# BalancingRobotFullSizePCB.net
KiCad netlist of a schematic drawn in EAGLE
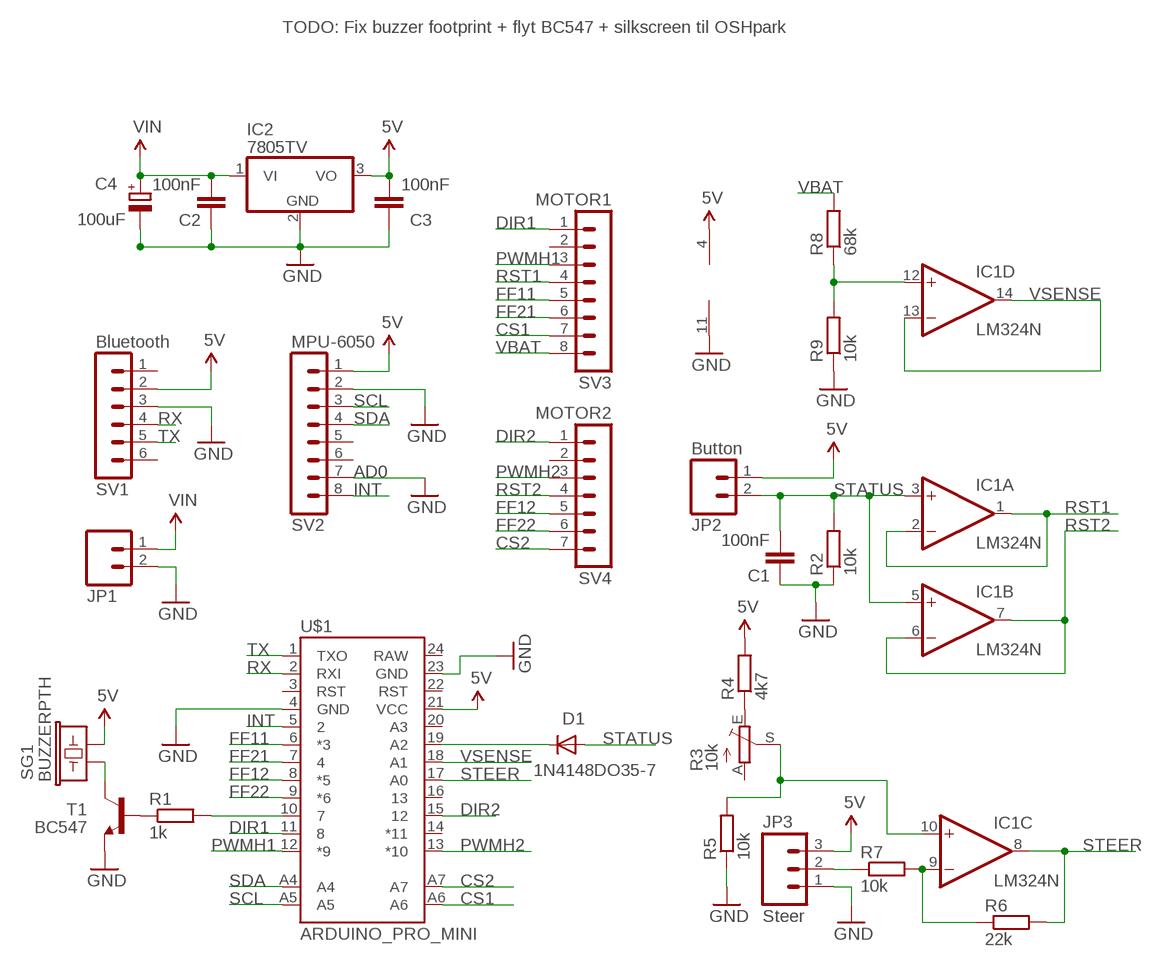
[diagram p0: schematic, sheet 1]

(export (version "E")
  (design (tool "Eeschema 10.0.6"))
  (components
    (comp (ref "C1")
      (value "100nF")
      (footprint "eagle-import:C025-025X050")
      (libsource (lib "eagle-import") (part "C-EU025-025X050"))
    )
    (comp (ref "C2")
      (value "100nF")
      (footprint "eagle-import:C025-025X050")
      (libsource (lib "eagle-import") (part "C-EU025-025X050"))
    )
    (comp (ref "C3")
      (value "100nF")
      (footprint "eagle-import:C025-025X050")
      (libsource (lib "eagle-import") (part "C-EU025-025X050"))
    )
    (comp (ref "C4")
      (value "100uF")
      (footprint "eagle-import:E2,5-5")
      (libsource (lib "eagle-import") (part "CPOL-EUE2.5-5"))
    )
    (comp (ref "D1")
      (value "1N4148DO35-7")
      (footprint "eagle-import:DO35-7")
      (libsource (lib "eagle-import") (part "1N4148DO35-7"))
    )
    (comp (ref "IC1")
      (value "LM324N")
      (footprint "eagle-import:DIL14")
      (libsource (lib "eagle-import") (part "LM324N"))
    )
    (comp (ref "IC2")
      (value "7805TV")
      (footprint "eagle-import:TO220V")
      (libsource (lib "eagle-import") (part "78TV05"))
    )
    (comp (ref "JP1")
      (value "M02PTH")
      (footprint "eagle-import:1X02")
      (libsource (lib "eagle-import") (part "M02PTH"))
    )
    (comp (ref "JP2")
      (value "Button")
      (footprint "eagle-import:1X02")
      (libsource (lib "eagle-import") (part "M02PTH"))
    )
    (comp (ref "JP3")
      (value "Steer")
      (footprint "eagle-import:1X03")
      (libsource (lib "eagle-import") (part "M03PTH"))
    )
    (comp (ref "R1")
      (value "1k")
      (footprint "eagle-import:0207_10")
      (libsource (lib "eagle-import") (part "R-EU_0207/10"))
    )
    (comp (ref "R2")
      (value "10k")
      (footprint "eagle-import:0207_10")
      (libsource (lib "eagle-import") (part "R-EU_0207/10"))
    )
    (comp (ref "R3")
      (value "10k")
      (footprint "eagle-import:B25P")
      (libsource (lib "eagle-import") (part "TRIM_EU-B25P"))
    )
    (comp (ref "R4")
      (value "4k7")
      (footprint "eagle-import:0207_10")
      (libsource (lib "eagle-import") (part "R-EU_0207/10"))
    )
    (comp (ref "R5")
      (value "10k")
      (footprint "eagle-import:0207_10")
      (libsource (lib "eagle-import") (part "R-EU_0207/10"))
    )
    (comp (ref "R6")
      (value "22k")
      (footprint "eagle-import:0207_10")
      (libsource (lib "eagle-import") (part "R-EU_0207/10"))
    )
    (comp (ref "R7")
      (value "10k")
      (footprint "eagle-import:0207_10")
      (libsource (lib "eagle-import") (part "R-EU_0207/10"))
    )
    (comp (ref "R8")
      (value "68k")
      (footprint "eagle-import:0207_10")
      (libsource (lib "eagle-import") (part "R-EU_0207/10"))
    )
    (comp (ref "R9")
      (value "10k")
      (footprint "eagle-import:0207_10")
      (libsource (lib "eagle-import") (part "R-EU_0207/10"))
    )
    (comp (ref "SG1")
      (value "BUZZERPTH")
      (footprint "eagle-import:BUZZER-12MM")
      (libsource (lib "eagle-import") (part "BUZZERPTH"))
    )
    (comp (ref "SV1")
      (value "Bluetooth")
      (footprint "eagle-import:MA06-1")
      (libsource (lib "eagle-import") (part "MA06-1"))
    )
    (comp (ref "SV2")
      (value "MPU-6050")
      (footprint "eagle-import:MA08-1")
      (libsource (lib "eagle-import") (part "MA08-1"))
    )
    (comp (ref "SV3")
      (value "MOTOR1")
      (footprint "eagle-import:MA08-1")
      (libsource (lib "eagle-import") (part "MA08-1"))
    )
    (comp (ref "SV4")
      (value "MOTOR2")
      (footprint "eagle-import:MA07-1")
      (libsource (lib "eagle-import") (part "MA07-1"))
    )
    (comp (ref "T1")
      (value "BC547")
      (footprint "eagle-import:TO92")
      (libsource (lib "eagle-import") (part "BC547"))
    )
    (comp (ref "U$1")
      (value "ARDUINO_PRO_MINI")
      (footprint "eagle-import:ARDUINO_PRO_MINI")
      (libsource (lib "eagle-import") (part "ARDUINO_PRO_MINI"))
    )
  )
  (nets
    (net (code "1") (name "/CS1") (class "Default")
      (node (ref "SV3") (pin "7") (pinfunction "7_7") (pintype "passive"))
      (node (ref "U$1") (pin "A6") (pinfunction "A6_A6") (pintype "bidirectional"))
    )
    (net (code "2") (name "/CS2") (class "Default")
      (node (ref "SV4") (pin "7") (pinfunction "7_7") (pintype "passive"))
      (node (ref "U$1") (pin "A7") (pinfunction "A7_A7") (pintype "bidirectional"))
    )
    (net (code "3") (name "/DIR1") (class "Default")
      (node (ref "SV3") (pin "1") (pinfunction "1_1") (pintype "passive"))
      (node (ref "U$1") (pin "11") (pinfunction "8_11") (pintype "bidirectional"))
    )
    (net (code "4") (name "/DIR2") (class "Default")
      (node (ref "SV4") (pin "1") (pinfunction "1_1") (pintype "passive"))
      (node (ref "U$1") (pin "15") (pinfunction "12_15") (pintype "bidirectional"))
    )
    (net (code "5") (name "/FF11") (class "Default")
      (node (ref "SV3") (pin "5") (pinfunction "5_5") (pintype "passive"))
      (node (ref "U$1") (pin "6") (pinfunction "*3_6") (pintype "bidirectional"))
    )
    (net (code "6") (name "/FF12") (class "Default")
      (node (ref "SV4") (pin "5") (pinfunction "5_5") (pintype "passive"))
      (node (ref "U$1") (pin "8") (pinfunction "*5_8") (pintype "bidirectional"))
    )
    (net (code "7") (name "/FF21") (class "Default")
      (node (ref "SV3") (pin "6") (pinfunction "6_6") (pintype "passive"))
      (node (ref "U$1") (pin "7") (pinfunction "4_7") (pintype "bidirectional"))
    )
    (net (code "8") (name "/FF22") (class "Default")
      (node (ref "SV4") (pin "6") (pinfunction "6_6") (pintype "passive"))
      (node (ref "U$1") (pin "9") (pinfunction "*6_9") (pintype "bidirectional"))
    )
    (net (code "9") (name "/INT") (class "Default")
      (node (ref "SV2") (pin "8") (pinfunction "8_8") (pintype "passive"))
      (node (ref "U$1") (pin "5") (pinfunction "2_5") (pintype "bidirectional"))
    )
    (net (code "10") (name "/PWMH1") (class "Default")
      (node (ref "SV3") (pin "3") (pinfunction "3_3") (pintype "passive"))
      (node (ref "U$1") (pin "12") (pinfunction "*9_12") (pintype "bidirectional"))
    )
    (net (code "11") (name "/PWMH2") (class "Default")
      (node (ref "SV4") (pin "3") (pinfunction "3_3") (pintype "passive"))
      (node (ref "U$1") (pin "13") (pinfunction "*10_13") (pintype "bidirectional"))
    )
    (net (code "12") (name "/RST1") (class "Default")
      (node (ref "IC1") (pin "1") (pinfunction "OUT_1") (pintype "output"))
      (node (ref "IC1") (pin "2") (pinfunction "-IN_2") (pintype "input"))
      (node (ref "SV3") (pin "4") (pinfunction "4_4") (pintype "passive"))
    )
    (net (code "13") (name "/RST2") (class "Default")
      (node (ref "IC1") (pin "6") (pinfunction "-IN_6") (pintype "input"))
      (node (ref "IC1") (pin "7") (pinfunction "OUT_7") (pintype "output"))
      (node (ref "SV4") (pin "4") (pinfunction "4_4") (pintype "passive"))
    )
    (net (code "14") (name "/RX") (class "Default")
      (node (ref "SV1") (pin "4") (pinfunction "4_4") (pintype "passive"))
      (node (ref "U$1") (pin "2") (pinfunction "RXI_2") (pintype "bidirectional"))
    )
    (net (code "15") (name "/SCL") (class "Default")
      (node (ref "SV2") (pin "3") (pinfunction "3_3") (pintype "passive"))
      (node (ref "U$1") (pin "A5") (pinfunction "A5_A5") (pintype "bidirectional"))
    )
    (net (code "16") (name "/SDA") (class "Default")
      (node (ref "SV2") (pin "4") (pinfunction "4_4") (pintype "passive"))
      (node (ref "U$1") (pin "A4") (pinfunction "A4_A4") (pintype "bidirectional"))
    )
    (net (code "17") (name "/STATUS") (class "Default")
      (node (ref "C1") (pin "2") (pinfunction "2_2") (pintype "passive"))
      (node (ref "D1") (pin "A") (pinfunction "A_A") (pintype "passive"))
      (node (ref "IC1") (pin "3") (pinfunction "+IN_3") (pintype "input"))
      (node (ref "IC1") (pin "5") (pinfunction "+IN_5") (pintype "input"))
      (node (ref "JP2") (pin "2") (pinfunction "2_2") (pintype "passive"))
      (node (ref "R2") (pin "2") (pinfunction "2_2") (pintype "passive"))
    )
    (net (code "18") (name "/STEER") (class "Default")
      (node (ref "IC1") (pin "8") (pinfunction "OUT_8") (pintype "output"))
      (node (ref "R6") (pin "2") (pinfunction "2_2") (pintype "passive"))
      (node (ref "U$1") (pin "17") (pinfunction "A0_17") (pintype "bidirectional"))
    )
    (net (code "19") (name "/TX") (class "Default")
      (node (ref "SV1") (pin "5") (pinfunction "5_5") (pintype "passive"))
      (node (ref "U$1") (pin "1") (pinfunction "TXO_1") (pintype "bidirectional"))
    )
    (net (code "20") (name "/VBAT") (class "Default")
      (node (ref "R8") (pin "2") (pinfunction "2_2") (pintype "passive"))
      (node (ref "SV3") (pin "8") (pinfunction "8_8") (pintype "passive"))
    )
    (net (code "21") (name "/VSENSE") (class "Default")
      (node (ref "IC1") (pin "13") (pinfunction "-IN_13") (pintype "input"))
      (node (ref "IC1") (pin "14") (pinfunction "OUT_14") (pintype "output"))
      (node (ref "U$1") (pin "18") (pinfunction "A1_18") (pintype "bidirectional"))
    )
    (net (code "22") (name "5V") (class "Default")
      (node (ref "C3") (pin "2") (pinfunction "2_2") (pintype "passive"))
      (node (ref "IC1") (pin "4") (pinfunction "V+_4") (pintype "power_in"))
      (node (ref "IC2") (pin "3") (pinfunction "VO_3") (pintype "passive"))
      (node (ref "JP2") (pin "1") (pinfunction "1_1") (pintype "passive"))
      (node (ref "JP3") (pin "3") (pinfunction "3_3") (pintype "passive"))
      (node (ref "R4") (pin "2") (pinfunction "2_2") (pintype "passive"))
      (node (ref "SG1") (pin "-") (pinfunction "2_-") (pintype "passive"))
      (node (ref "SV1") (pin "2") (pinfunction "2_2") (pintype "passive"))
      (node (ref "SV2") (pin "1") (pinfunction "1_1") (pintype "passive"))
      (node (ref "U$1") (pin "21") (pinfunction "VCC_21") (pintype "bidirectional"))
    )
    (net (code "23") (name "GND") (class "Default")
      (node (ref "C1") (pin "1") (pinfunction "1_1") (pintype "passive"))
      (node (ref "C2") (pin "1") (pinfunction "1_1") (pintype "passive"))
      (node (ref "C3") (pin "1") (pinfunction "1_1") (pintype "passive"))
      (node (ref "C4") (pin "-") (pinfunction "-_-") (pintype "passive"))
      (node (ref "IC1") (pin "11") (pinfunction "V-_11") (pintype "power_in"))
      (node (ref "IC2") (pin "2") (pinfunction "GND_2") (pintype "passive"))
      (node (ref "JP1") (pin "2") (pinfunction "2_2") (pintype "passive"))
      (node (ref "JP3") (pin "1") (pinfunction "1_1") (pintype "passive"))
      (node (ref "R2") (pin "1") (pinfunction "1_1") (pintype "passive"))
      (node (ref "R5") (pin "1") (pinfunction "1_1") (pintype "passive"))
      (node (ref "R9") (pin "1") (pinfunction "1_1") (pintype "passive"))
      (node (ref "SV1") (pin "3") (pinfunction "3_3") (pintype "passive"))
      (node (ref "SV2") (pin "2") (pinfunction "2_2") (pintype "passive"))
      (node (ref "SV2") (pin "7") (pinfunction "7_7") (pintype "passive"))
      (node (ref "T1") (pin "1") (pinfunction "E_1") (pintype "passive"))
      (node (ref "U$1") (pin "23") (pinfunction "GND_23") (pintype "bidirectional"))
      (node (ref "U$1") (pin "4") (pinfunction "GND_4") (pintype "bidirectional"))
    )
    (net (code "24") (name "Net-(IC1C-+IN)") (class "Default")
      (node (ref "IC1") (pin "10") (pinfunction "+IN_10") (pintype "input"))
      (node (ref "R3") (pin "S") (pinfunction "S_S") (pintype "passive"))
      (node (ref "R5") (pin "2") (pinfunction "2_2") (pintype "passive"))
    )
    (net (code "25") (name "Net-(IC1C--IN)") (class "Default")
      (node (ref "IC1") (pin "9") (pinfunction "-IN_9") (pintype "input"))
      (node (ref "R6") (pin "1") (pinfunction "1_1") (pintype "passive"))
      (node (ref "R7") (pin "2") (pinfunction "2_2") (pintype "passive"))
    )
    (net (code "26") (name "Net-(IC1D-+IN)") (class "Default")
      (node (ref "IC1") (pin "12") (pinfunction "+IN_12") (pintype "input"))
      (node (ref "R8") (pin "1") (pinfunction "1_1") (pintype "passive"))
      (node (ref "R9") (pin "2") (pinfunction "2_2") (pintype "passive"))
    )
    (net (code "27") (name "Net-(JP3-Pad2)") (class "Default")
      (node (ref "JP3") (pin "2") (pinfunction "2_2") (pintype "passive"))
      (node (ref "R7") (pin "1") (pinfunction "1_1") (pintype "passive"))
    )
    (net (code "28") (name "Net-(R3-PadE)") (class "Default")
      (node (ref "R3") (pin "E") (pinfunction "E_E") (pintype "passive"))
      (node (ref "R4") (pin "1") (pinfunction "1_1") (pintype "passive"))
    )
    (net (code "29") (name "Net-(SG1-1)") (class "Default")
      (node (ref "SG1") (pin "+") (pinfunction "1_+") (pintype "passive"))
      (node (ref "T1") (pin "3") (pinfunction "C_3") (pintype "passive"))
    )
    (net (code "30") (name "Net-(T1-B)") (class "Default")
      (node (ref "R1") (pin "1") (pinfunction "1_1") (pintype "passive"))
      (node (ref "T1") (pin "2") (pinfunction "B_2") (pintype "passive"))
    )
    (net (code "31") (name "Net-(U$1-7)") (class "Default")
      (node (ref "R1") (pin "2") (pinfunction "2_2") (pintype "passive"))
      (node (ref "U$1") (pin "10") (pinfunction "7_10") (pintype "bidirectional"))
    )
    (net (code "32") (name "Net-(U$1-A2)") (class "Default")
      (node (ref "D1") (pin "C") (pinfunction "C_C") (pintype "passive"))
      (node (ref "U$1") (pin "19") (pinfunction "A2_19") (pintype "bidirectional"))
    )
    (net (code "33") (name "VIN") (class "Default")
      (node (ref "C2") (pin "2") (pinfunction "2_2") (pintype "passive"))
      (node (ref "C4") (pin "+") (pinfunction "+_+") (pintype "passive"))
      (node (ref "IC2") (pin "1") (pinfunction "VI_1") (pintype "input"))
      (node (ref "JP1") (pin "1") (pinfunction "1_1") (pintype "passive"))
    )
    (net (code "34") (name "unconnected-(R3-PadA)") (class "Default")
      (node (ref "R3") (pin "A") (pinfunction "A_A") (pintype "passive"))
    )
    (net (code "35") (name "unconnected-(SV1-Pad1)") (class "Default")
      (node (ref "SV1") (pin "1") (pinfunction "1_1") (pintype "passive"))
    )
    (net (code "36") (name "unconnected-(SV1-Pad6)") (class "Default")
      (node (ref "SV1") (pin "6") (pinfunction "6_6") (pintype "passive"))
    )
    (net (code "37") (name "unconnected-(SV2-Pad5)") (class "Default")
      (node (ref "SV2") (pin "5") (pinfunction "5_5") (pintype "passive"))
    )
    (net (code "38") (name "unconnected-(SV2-Pad6)") (class "Default")
      (node (ref "SV2") (pin "6") (pinfunction "6_6") (pintype "passive"))
    )
    (net (code "39") (name "unconnected-(SV3-Pad2)") (class "Default")
      (node (ref "SV3") (pin "2") (pinfunction "2_2") (pintype "passive"))
    )
    (net (code "40") (name "unconnected-(SV4-Pad2)") (class "Default")
      (node (ref "SV4") (pin "2") (pinfunction "2_2") (pintype "passive"))
    )
    (net (code "41") (name "unconnected-(U$1-*11-Pad14)") (class "Default")
      (node (ref "U$1") (pin "14") (pinfunction "*11_14") (pintype "bidirectional"))
    )
    (net (code "42") (name "unconnected-(U$1-13-Pad16)") (class "Default")
      (node (ref "U$1") (pin "16") (pinfunction "13_16") (pintype "bidirectional"))
    )
    (net (code "43") (name "unconnected-(U$1-A3-Pad20)") (class "Default")
      (node (ref "U$1") (pin "20") (pinfunction "A3_20") (pintype "bidirectional"))
    )
    (net (code "44") (name "unconnected-(U$1-RAW-Pad24)") (class "Default")
      (node (ref "U$1") (pin "24") (pinfunction "RAW_24") (pintype "bidirectional"))
    )
    (net (code "45") (name "unconnected-(U$1-RST-Pad3)") (class "Default")
      (node (ref "U$1") (pin "3") (pinfunction "RST_3") (pintype "bidirectional"))
    )
    (net (code "46") (name "unconnected-(U$1-RST-Pad22)") (class "Default")
      (node (ref "U$1") (pin "22") (pinfunction "RST_22") (pintype "bidirectional"))
    )
  )
)
